# Micro_SD.net
KiCad netlist of a schematic drawn in Altium Designer
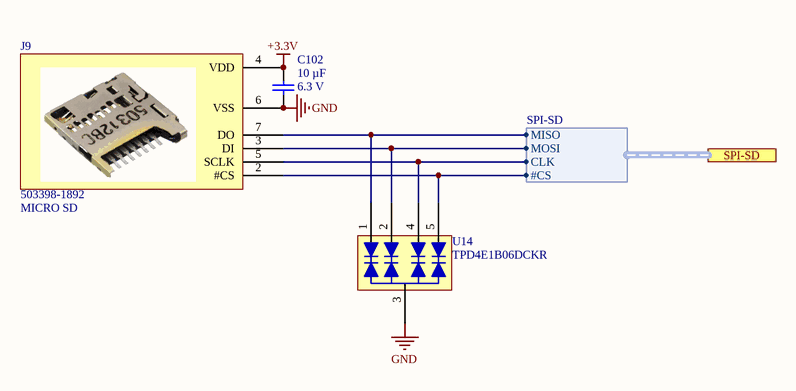
[diagram p0: Micro SD.SchDoc]

(export (version "E")
  (design (tool "Eeschema 10.0.6"))
  (components
    (comp (ref "C102")
      (value "50V")
      (footprint "0603C")
      (description "CAP .1UF 50V CERAMIC Y5V 0805")
      (fields
        (field (name "MANUFACTURER") "Samsung")
        (field (name "MANUFACTURER PART NUMBER") "CL10B106MQ8NRNC")
        (field (name "CAPACITANCE") "10 µF")
        (field (name "RATED VOLTAGE") "6.3 V")
      )
      (libsource (lib "Miscellaneous Devices") (part "Cap"))
    )
    (comp (ref "J9")
      (value "MICRO SD")
      (footprint "503398-1892")
      (fields (field (name "MANUFACTURER") "Molex") (field (name "MANUFACTURER PART NUMBER") "503398-1892"))
      (libsource (lib "LUCHADOR SCHLIB") (part "503398-1892"))
    )
    (comp (ref "U14")
      (value "TPD4E1B06DCKR")
      (footprint "SC70-6")
      (fields
        (field (name "MANUFACTURER") "Texas Instruments")
        (field (name "MANUFACTURER PART NUMBER") "TPD4E1B06DCKR")
      )
      (libsource (lib "LUCHADOR SCHLIB") (part "TPD4E1B06DCKR"))
    )
  )
  (nets
    (net (code "2") (name "+3.3V") (class "Default")
      (node (ref "C102") (pin "1") (pinfunction "1_1") (pintype "passive"))
      (node (ref "J9") (pin "4") (pinfunction "VDD_4") (pintype "passive"))
    )
    (net (code "4") (name "GND") (class "Default")
      (node (ref "C102") (pin "2") (pinfunction "2_2") (pintype "passive"))
      (node (ref "J9") (pin "6") (pinfunction "VSS_6") (pintype "passive"))
      (node (ref "U14") (pin "3") (pinfunction "GND_3") (pintype "passive"))
    )
    (net (code "5") (name "Net-(J9-#CS)") (class "Default")
      (node (ref "J9") (pin "2") (pinfunction "#CS_2") (pintype "passive"))
      (node (ref "U14") (pin "5") (pinfunction "IO4_5") (pintype "passive"))
    )
    (net (code "6") (name "Net-(J9-DI)") (class "Default")
      (node (ref "J9") (pin "3") (pinfunction "DI_3") (pintype "passive"))
      (node (ref "U14") (pin "2") (pinfunction "IO2_2") (pintype "passive"))
    )
    (net (code "7") (name "Net-(J9-DO)") (class "Default")
      (node (ref "J9") (pin "7") (pinfunction "DO_7") (pintype "passive"))
      (node (ref "U14") (pin "1") (pinfunction "IO1_1") (pintype "passive"))
    )
    (net (code "8") (name "Net-(J9-SCLK)") (class "Default")
      (node (ref "J9") (pin "5") (pinfunction "SCLK_5") (pintype "passive"))
      (node (ref "U14") (pin "4") (pinfunction "IO3_4") (pintype "passive"))
    )
  )
)
